# light_key_control.net
KiCad netlist of a schematic drawn in Altium Designer
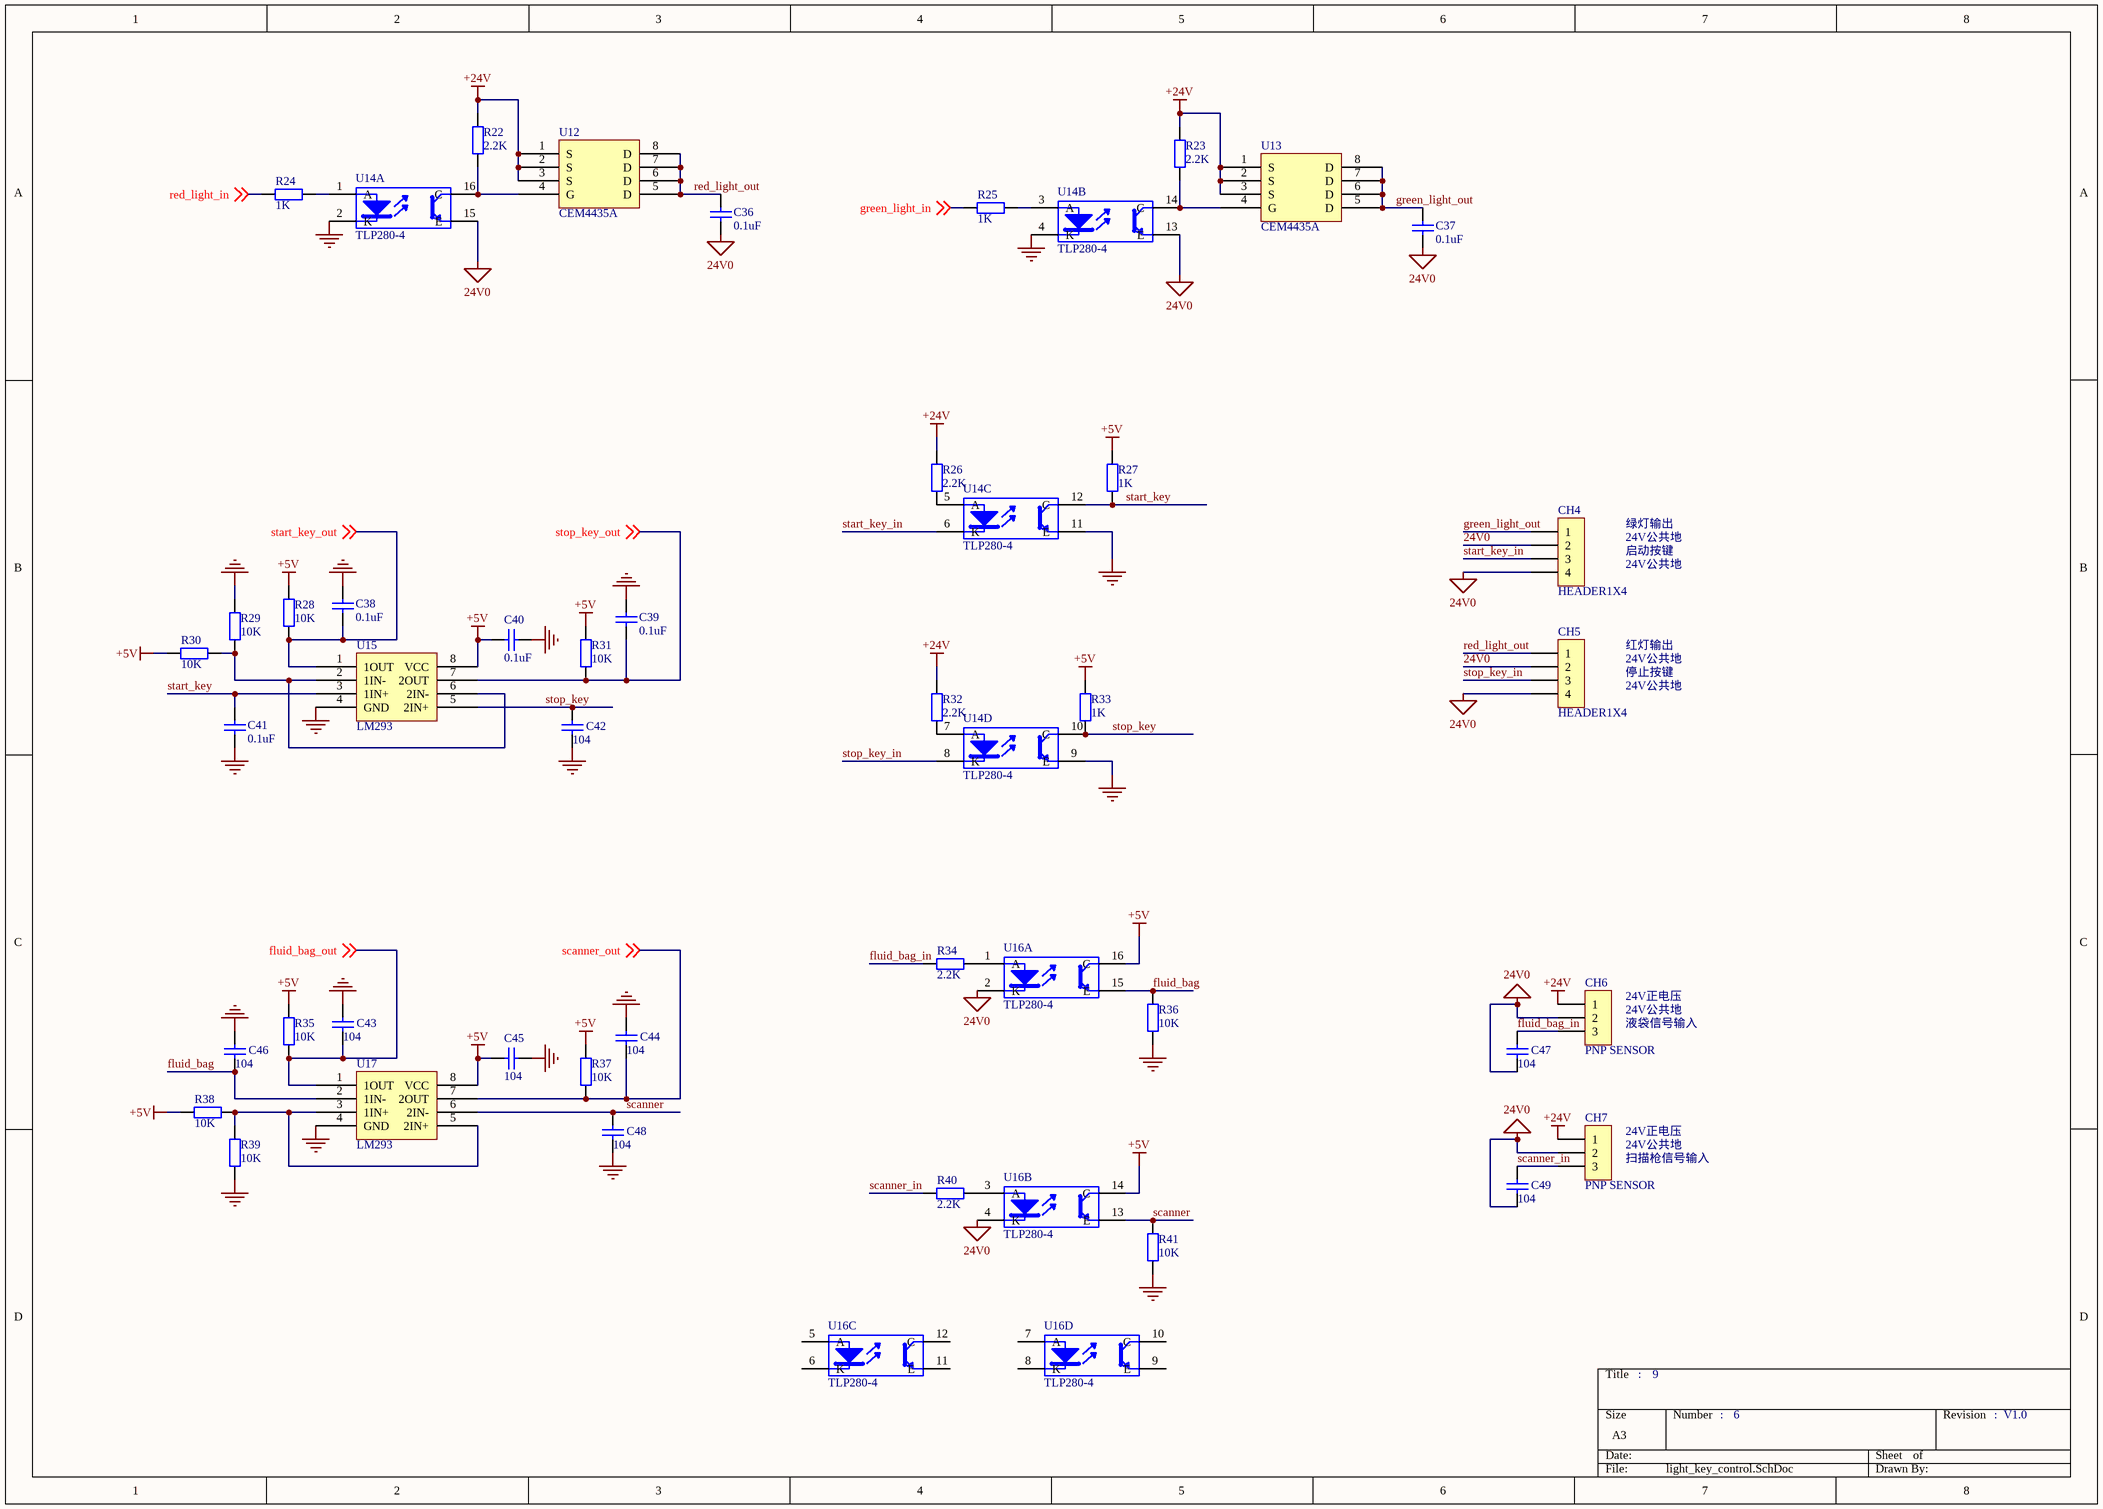
[diagram p0: light_key_control.SchDoc]

(export (version "E")
  (design (tool "Eeschema 10.0.6"))
  (components
    (comp (ref "C36")
      (value "0.1uF")
      (footprint "0805")
      (description "Capacitor")
      (fields (field (name "Comment") "Cap") (field (name "PUBLISHER") "Altium Limited"))
      (libsource (lib "Miscellaneous Devices") (part "Cap"))
    )
    (comp (ref "C37")
      (value "0.1uF")
      (footprint "0805")
      (description "Capacitor")
      (fields (field (name "Comment") "Cap") (field (name "PUBLISHER") "Altium Limited"))
      (libsource (lib "Miscellaneous Devices") (part "Cap"))
    )
    (comp (ref "C38")
      (value "0.1uF")
      (footprint "0805")
      (description "Capacitor")
      (fields (field (name "Comment") "Cap") (field (name "PUBLISHER") "Altium Limited"))
      (libsource (lib "Miscellaneous Devices") (part "Cap"))
    )
    (comp (ref "C39")
      (value "0.1uF")
      (footprint "0805")
      (description "Capacitor")
      (fields (field (name "Comment") "Cap") (field (name "PUBLISHER") "Altium Limited"))
      (libsource (lib "Miscellaneous Devices") (part "Cap"))
    )
    (comp (ref "C40")
      (value "0.1uF")
      (footprint "0805")
      (description "Capacitor")
      (fields (field (name "Comment") "Cap") (field (name "PUBLISHER") "Altium Limited"))
      (libsource (lib "Miscellaneous Devices") (part "Cap"))
    )
    (comp (ref "C41")
      (value "0.1uF")
      (footprint "0805")
      (description "Capacitor")
      (fields (field (name "Comment") "Cap") (field (name "PUBLISHER") "Altium Limited"))
      (libsource (lib "Miscellaneous Devices") (part "Cap"))
    )
    (comp (ref "C42")
      (value "104")
      (footprint "0805")
      (description "Capacitor")
      (fields (field (name "Comment") "Cap") (field (name "PUBLISHER") "Altium Limited"))
      (libsource (lib "Miscellaneous Devices") (part "Cap"))
    )
    (comp (ref "C43")
      (value "104")
      (footprint "0805")
      (description "Capacitor")
      (fields (field (name "Comment") "Cap") (field (name "PUBLISHER") "Altium Limited"))
      (libsource (lib "Miscellaneous Devices") (part "Cap"))
    )
    (comp (ref "C44")
      (value "104")
      (footprint "0805")
      (description "Capacitor")
      (fields (field (name "Comment") "Cap") (field (name "PUBLISHER") "Altium Limited"))
      (libsource (lib "Miscellaneous Devices") (part "Cap"))
    )
    (comp (ref "C45")
      (value "104")
      (footprint "0805")
      (description "Capacitor")
      (fields (field (name "Comment") "Cap") (field (name "PUBLISHER") "Altium Limited"))
      (libsource (lib "Miscellaneous Devices") (part "Cap"))
    )
    (comp (ref "C46")
      (value "104")
      (footprint "0805")
      (description "Capacitor")
      (fields (field (name "Comment") "Cap") (field (name "PUBLISHER") "Altium Limited"))
      (libsource (lib "Miscellaneous Devices") (part "Cap"))
    )
    (comp (ref "C47")
      (value "104")
      (footprint "0805")
      (description "Capacitor")
      (fields (field (name "Comment") "Cap") (field (name "PUBLISHER") "Altium Limited"))
      (libsource (lib "Miscellaneous Devices") (part "Cap"))
    )
    (comp (ref "C48")
      (value "104")
      (footprint "0805")
      (description "Capacitor")
      (fields (field (name "Comment") "Cap") (field (name "PUBLISHER") "Altium Limited"))
      (libsource (lib "Miscellaneous Devices") (part "Cap"))
    )
    (comp (ref "C49")
      (value "104")
      (footprint "0805")
      (description "Capacitor")
      (fields (field (name "Comment") "Cap") (field (name "PUBLISHER") "Altium Limited"))
      (libsource (lib "Miscellaneous Devices") (part "Cap"))
    )
    (comp (ref "CH4")
      (value "HEADER1X4")
      (footprint "CH3.96-4PIN")
      (libsource (lib "myIntegrated_Library1") (part "HEADER1X4"))
    )
    (comp (ref "CH5")
      (value "HEADER1X4")
      (footprint "CH3.96-4PIN")
      (libsource (lib "myIntegrated_Library1") (part "HEADER1X4"))
    )
    (comp (ref "CH6")
      (value "HEADER1X3")
      (footprint "CH3.96-3PIN")
      (fields (field (name "ALTIUM_UNNAMED_1") "PNP SENSOR"))
      (libsource (lib "myIntegrated_Library1") (part "HEADER1X3"))
    )
    (comp (ref "CH7")
      (value "HEADER1X3")
      (footprint "CH3.96-3PIN")
      (fields (field (name "ALTIUM_UNNAMED_1") "PNP SENSOR"))
      (libsource (lib "myIntegrated_Library1") (part "HEADER1X3"))
    )
    (comp (ref "R22")
      (value "2.2K")
      (footprint "0805")
      (description "Resistor")
      (fields (field (name "Comment") "Res2") (field (name "PUBLISHER") "Altium Limited"))
      (libsource (lib "") (part "Res2_1"))
    )
    (comp (ref "R23")
      (value "2.2K")
      (footprint "0805")
      (description "Resistor")
      (fields (field (name "Comment") "Res2") (field (name "PUBLISHER") "Altium Limited"))
      (libsource (lib "") (part "Res2_1"))
    )
    (comp (ref "R24")
      (value "1K")
      (footprint "0805")
      (description "Resistor")
      (fields (field (name "Comment") "Res2") (field (name "PUBLISHER") "Altium Limited"))
      (libsource (lib "") (part "Res2_3"))
    )
    (comp (ref "R25")
      (value "1K")
      (footprint "0805")
      (description "Resistor")
      (fields (field (name "Comment") "Res2") (field (name "PUBLISHER") "Altium Limited"))
      (libsource (lib "") (part "Res2_3"))
    )
    (comp (ref "R26")
      (value "2.2K")
      (footprint "0805")
      (description "Resistor")
      (fields (field (name "Comment") "Res2") (field (name "PUBLISHER") "Altium Limited"))
      (libsource (lib "Miscellaneous Devices") (part "Res2"))
    )
    (comp (ref "R27")
      (value "1K")
      (footprint "0805")
      (description "Resistor")
      (fields (field (name "Comment") "Res2") (field (name "PUBLISHER") "Altium Limited"))
      (libsource (lib "Miscellaneous Devices") (part "Res2"))
    )
    (comp (ref "R28")
      (value "10K")
      (footprint "0805")
      (description "Resistor")
      (fields (field (name "Comment") "Res2") (field (name "PUBLISHER") "Altium Limited"))
      (libsource (lib "Miscellaneous Devices") (part "Res2"))
    )
    (comp (ref "R29")
      (value "10K")
      (footprint "0805")
      (description "Resistor")
      (fields (field (name "Comment") "Res2") (field (name "PUBLISHER") "Altium Limited"))
      (libsource (lib "Miscellaneous Devices") (part "Res2"))
    )
    (comp (ref "R30")
      (value "10K")
      (footprint "0805")
      (description "Resistor")
      (fields (field (name "Comment") "Res2") (field (name "PUBLISHER") "Altium Limited"))
      (libsource (lib "") (part "Res2_2"))
    )
    (comp (ref "R31")
      (value "10K")
      (footprint "0805")
      (description "Resistor")
      (fields (field (name "Comment") "Res2") (field (name "PUBLISHER") "Altium Limited"))
      (libsource (lib "Miscellaneous Devices") (part "Res2"))
    )
    (comp (ref "R32")
      (value "2.2K")
      (footprint "0805")
      (description "Resistor")
      (fields (field (name "Comment") "Res2") (field (name "PUBLISHER") "Altium Limited"))
      (libsource (lib "Miscellaneous Devices") (part "Res2"))
    )
    (comp (ref "R33")
      (value "1K")
      (footprint "0805")
      (description "Resistor")
      (fields (field (name "Comment") "Res2") (field (name "PUBLISHER") "Altium Limited"))
      (libsource (lib "Miscellaneous Devices") (part "Res2"))
    )
    (comp (ref "R34")
      (value "2.2K")
      (footprint "0805")
      (description "Resistor")
      (fields (field (name "Comment") "Res2") (field (name "PUBLISHER") "Altium Limited"))
      (libsource (lib "") (part "Res2_2"))
    )
    (comp (ref "R35")
      (value "10K")
      (footprint "0805")
      (description "Resistor")
      (fields (field (name "Comment") "Res2") (field (name "PUBLISHER") "Altium Limited"))
      (libsource (lib "Miscellaneous Devices") (part "Res2"))
    )
    (comp (ref "R36")
      (value "10K")
      (footprint "0805")
      (description "Resistor")
      (fields (field (name "Comment") "Res2") (field (name "PUBLISHER") "Altium Limited"))
      (libsource (lib "Miscellaneous Devices") (part "Res2"))
    )
    (comp (ref "R37")
      (value "10K")
      (footprint "0805")
      (description "Resistor")
      (fields (field (name "Comment") "Res2") (field (name "PUBLISHER") "Altium Limited"))
      (libsource (lib "Miscellaneous Devices") (part "Res2"))
    )
    (comp (ref "R38")
      (value "10K")
      (footprint "0805")
      (description "Resistor")
      (fields (field (name "Comment") "Res2") (field (name "PUBLISHER") "Altium Limited"))
      (libsource (lib "") (part "Res2_2"))
    )
    (comp (ref "R39")
      (value "10K")
      (footprint "0805")
      (description "Resistor")
      (fields (field (name "Comment") "Res2") (field (name "PUBLISHER") "Altium Limited"))
      (libsource (lib "Miscellaneous Devices") (part "Res2"))
    )
    (comp (ref "R40")
      (value "2.2K")
      (footprint "0805")
      (description "Resistor")
      (fields (field (name "Comment") "Res2") (field (name "PUBLISHER") "Altium Limited"))
      (libsource (lib "") (part "Res2_2"))
    )
    (comp (ref "R41")
      (value "10K")
      (footprint "0805")
      (description "Resistor")
      (fields (field (name "Comment") "Res2") (field (name "PUBLISHER") "Altium Limited"))
      (libsource (lib "Miscellaneous Devices") (part "Res2"))
    )
    (comp (ref "U12")
      (value "CEM4435A")
      (footprint "SOP8-OP27")
      (libsource (lib "myIntegrated_Library1") (part "CEM4435A"))
    )
    (comp (ref "U13")
      (value "CEM4435A")
      (footprint "SOP8-OP27")
      (libsource (lib "myIntegrated_Library1") (part "CEM4435A"))
    )
    (comp (ref "U14") (value "TLP280-4") (footprint "SO16") (libsource (lib "WH V20") (part "TLP521-4")))
    (comp (ref "U15")
      (value "LM293")
      (footprint "SOP8-OP27")
      (libsource (lib "myIntegrated_Library1") (part "LM293"))
    )
    (comp (ref "U16") (value "TLP280-4") (footprint "SO16") (libsource (lib "WH V20") (part "TLP521-4")))
    (comp (ref "U17")
      (value "LM293")
      (footprint "SOP8-OP27")
      (libsource (lib "myIntegrated_Library1") (part "LM293"))
    )
  )
  (nets
    (net (code "1") (name "+5V") (class "Default")
      (node (ref "C40") (pin "2") (pinfunction "2_2") (pintype "passive"))
      (node (ref "C45") (pin "2") (pinfunction "2_2") (pintype "passive"))
      (node (ref "R27") (pin "1") (pinfunction "1_1") (pintype "passive"))
      (node (ref "R28") (pin "1") (pinfunction "1_1") (pintype "passive"))
      (node (ref "R30") (pin "1") (pinfunction "1_1") (pintype "passive"))
      (node (ref "R31") (pin "1") (pinfunction "1_1") (pintype "passive"))
      (node (ref "R33") (pin "1") (pinfunction "1_1") (pintype "passive"))
      (node (ref "R35") (pin "1") (pinfunction "1_1") (pintype "passive"))
      (node (ref "R37") (pin "1") (pinfunction "1_1") (pintype "passive"))
      (node (ref "R38") (pin "1") (pinfunction "1_1") (pintype "passive"))
      (node (ref "U15") (pin "8") (pinfunction "VCC_8") (pintype "passive"))
      (node (ref "U16") (pin "14") (pinfunction "C_14") (pintype "passive"))
      (node (ref "U16") (pin "16") (pinfunction "C_16") (pintype "passive"))
      (node (ref "U17") (pin "8") (pinfunction "VCC_8") (pintype "passive"))
    )
    (net (code "2") (name "+24V") (class "Default")
      (node (ref "CH6") (pin "1") (pinfunction "1_1") (pintype "passive"))
      (node (ref "CH7") (pin "1") (pinfunction "1_1") (pintype "passive"))
      (node (ref "R22") (pin "2") (pinfunction "2_2") (pintype "passive"))
      (node (ref "R23") (pin "2") (pinfunction "2_2") (pintype "passive"))
      (node (ref "R26") (pin "1") (pinfunction "1_1") (pintype "passive"))
      (node (ref "R32") (pin "1") (pinfunction "1_1") (pintype "passive"))
      (node (ref "U12") (pin "1") (pinfunction "S_1") (pintype "passive"))
      (node (ref "U12") (pin "2") (pinfunction "S_2") (pintype "passive"))
      (node (ref "U12") (pin "3") (pinfunction "S_3") (pintype "passive"))
      (node (ref "U13") (pin "1") (pinfunction "S_1") (pintype "passive"))
      (node (ref "U13") (pin "2") (pinfunction "S_2") (pintype "passive"))
      (node (ref "U13") (pin "3") (pinfunction "S_3") (pintype "passive"))
    )
    (net (code "3") (name "/fluid_bag") (class "Default")
      (node (ref "C46") (pin "1") (pinfunction "1_1") (pintype "passive"))
      (node (ref "R36") (pin "1") (pinfunction "1_1") (pintype "passive"))
      (node (ref "U16") (pin "15") (pinfunction "E_15") (pintype "passive"))
      (node (ref "U17") (pin "2") (pinfunction "1IN-_2") (pintype "passive"))
    )
    (net (code "4") (name "/fluid_bag_in") (class "Default")
      (node (ref "C47") (pin "2") (pinfunction "2_2") (pintype "passive"))
      (node (ref "CH6") (pin "3") (pinfunction "3_3") (pintype "passive"))
      (node (ref "R34") (pin "1") (pinfunction "1_1") (pintype "passive"))
    )
    (net (code "5") (name "/green_light_out") (class "Default")
      (node (ref "C37") (pin "1") (pinfunction "1_1") (pintype "passive"))
      (node (ref "CH4") (pin "1") (pinfunction "1_1") (pintype "passive"))
      (node (ref "U13") (pin "5") (pinfunction "D_5") (pintype "passive"))
      (node (ref "U13") (pin "6") (pinfunction "D_6") (pintype "passive"))
      (node (ref "U13") (pin "7") (pinfunction "D_7") (pintype "passive"))
      (node (ref "U13") (pin "8") (pinfunction "D_8") (pintype "passive"))
    )
    (net (code "6") (name "/red_light_out") (class "Default")
      (node (ref "C36") (pin "1") (pinfunction "1_1") (pintype "passive"))
      (node (ref "CH5") (pin "1") (pinfunction "1_1") (pintype "passive"))
      (node (ref "U12") (pin "5") (pinfunction "D_5") (pintype "passive"))
      (node (ref "U12") (pin "6") (pinfunction "D_6") (pintype "passive"))
      (node (ref "U12") (pin "7") (pinfunction "D_7") (pintype "passive"))
      (node (ref "U12") (pin "8") (pinfunction "D_8") (pintype "passive"))
    )
    (net (code "7") (name "/scanner") (class "Default")
      (node (ref "C48") (pin "2") (pinfunction "2_2") (pintype "passive"))
      (node (ref "R41") (pin "1") (pinfunction "1_1") (pintype "passive"))
      (node (ref "U16") (pin "13") (pinfunction "E_13") (pintype "passive"))
      (node (ref "U17") (pin "6") (pinfunction "2IN-_6") (pintype "passive"))
    )
    (net (code "8") (name "/scanner_in") (class "Default")
      (node (ref "C49") (pin "2") (pinfunction "2_2") (pintype "passive"))
      (node (ref "CH7") (pin "3") (pinfunction "3_3") (pintype "passive"))
      (node (ref "R40") (pin "1") (pinfunction "1_1") (pintype "passive"))
    )
    (net (code "9") (name "/start_key") (class "Default")
      (node (ref "C41") (pin "2") (pinfunction "2_2") (pintype "passive"))
      (node (ref "R27") (pin "2") (pinfunction "2_2") (pintype "passive"))
      (node (ref "U14") (pin "12") (pinfunction "C_12") (pintype "passive"))
      (node (ref "U15") (pin "3") (pinfunction "1IN+_3") (pintype "passive"))
    )
    (net (code "10") (name "/start_key_in") (class "Default")
      (node (ref "CH4") (pin "3") (pinfunction "3_3") (pintype "passive"))
      (node (ref "U14") (pin "6") (pinfunction "K_6") (pintype "passive"))
    )
    (net (code "11") (name "/stop_key") (class "Default")
      (node (ref "C42") (pin "2") (pinfunction "2_2") (pintype "passive"))
      (node (ref "R33") (pin "2") (pinfunction "2_2") (pintype "passive"))
      (node (ref "U14") (pin "10") (pinfunction "C_10") (pintype "passive"))
      (node (ref "U15") (pin "5") (pinfunction "2IN+_5") (pintype "passive"))
    )
    (net (code "12") (name "/stop_key_in") (class "Default")
      (node (ref "CH5") (pin "3") (pinfunction "3_3") (pintype "passive"))
      (node (ref "U14") (pin "8") (pinfunction "K_8") (pintype "passive"))
    )
    (net (code "13") (name "24V0") (class "Default")
      (node (ref "C36") (pin "2") (pinfunction "2_2") (pintype "passive"))
      (node (ref "C37") (pin "2") (pinfunction "2_2") (pintype "passive"))
      (node (ref "C47") (pin "1") (pinfunction "1_1") (pintype "passive"))
      (node (ref "C49") (pin "1") (pinfunction "1_1") (pintype "passive"))
      (node (ref "CH4") (pin "2") (pinfunction "2_2") (pintype "passive"))
      (node (ref "CH4") (pin "4") (pinfunction "4_4") (pintype "passive"))
      (node (ref "CH5") (pin "2") (pinfunction "2_2") (pintype "passive"))
      (node (ref "CH5") (pin "4") (pinfunction "4_4") (pintype "passive"))
      (node (ref "CH6") (pin "2") (pinfunction "2_2") (pintype "passive"))
      (node (ref "CH7") (pin "2") (pinfunction "2_2") (pintype "passive"))
      (node (ref "U14") (pin "13") (pinfunction "E_13") (pintype "passive"))
      (node (ref "U14") (pin "15") (pinfunction "E_15") (pintype "passive"))
      (node (ref "U16") (pin "2") (pinfunction "K_2") (pintype "passive"))
      (node (ref "U16") (pin "4") (pinfunction "K_4") (pintype "passive"))
    )
    (net (code "14") (name "GND") (class "Default")
      (node (ref "C38") (pin "1") (pinfunction "1_1") (pintype "passive"))
      (node (ref "C39") (pin "1") (pinfunction "1_1") (pintype "passive"))
      (node (ref "C40") (pin "1") (pinfunction "1_1") (pintype "passive"))
      (node (ref "C41") (pin "1") (pinfunction "1_1") (pintype "passive"))
      (node (ref "C42") (pin "1") (pinfunction "1_1") (pintype "passive"))
      (node (ref "C43") (pin "2") (pinfunction "2_2") (pintype "passive"))
      (node (ref "C44") (pin "2") (pinfunction "2_2") (pintype "passive"))
      (node (ref "C45") (pin "1") (pinfunction "1_1") (pintype "passive"))
      (node (ref "C46") (pin "2") (pinfunction "2_2") (pintype "passive"))
      (node (ref "C48") (pin "1") (pinfunction "1_1") (pintype "passive"))
      (node (ref "R29") (pin "1") (pinfunction "1_1") (pintype "passive"))
      (node (ref "R36") (pin "2") (pinfunction "2_2") (pintype "passive"))
      (node (ref "R39") (pin "2") (pinfunction "2_2") (pintype "passive"))
      (node (ref "R41") (pin "2") (pinfunction "2_2") (pintype "passive"))
      (node (ref "U14") (pin "11") (pinfunction "E_11") (pintype "passive"))
      (node (ref "U14") (pin "2") (pinfunction "K_2") (pintype "passive"))
      (node (ref "U14") (pin "4") (pinfunction "K_4") (pintype "passive"))
      (node (ref "U14") (pin "9") (pinfunction "E_9") (pintype "passive"))
      (node (ref "U15") (pin "4") (pinfunction "GND_4") (pintype "passive"))
      (node (ref "U17") (pin "4") (pinfunction "GND_4") (pintype "passive"))
    )
    (net (code "15") (name "Net-(U12-G)") (class "Default")
      (node (ref "R22") (pin "1") (pinfunction "1_1") (pintype "passive"))
      (node (ref "U12") (pin "4") (pinfunction "G_4") (pintype "passive"))
      (node (ref "U14") (pin "16") (pinfunction "C_16") (pintype "passive"))
    )
    (net (code "16") (name "Net-(U13-G)") (class "Default")
      (node (ref "R23") (pin "1") (pinfunction "1_1") (pintype "passive"))
      (node (ref "U13") (pin "4") (pinfunction "G_4") (pintype "passive"))
      (node (ref "U14") (pin "14") (pinfunction "C_14") (pintype "passive"))
    )
    (net (code "17") (name "Net-(U14A-A)") (class "Default")
      (node (ref "R24") (pin "1") (pinfunction "1_1") (pintype "passive"))
      (node (ref "U14") (pin "1") (pinfunction "A_1") (pintype "passive"))
    )
    (net (code "18") (name "Net-(U14B-A)") (class "Default")
      (node (ref "R25") (pin "1") (pinfunction "1_1") (pintype "passive"))
      (node (ref "U14") (pin "3") (pinfunction "A_3") (pintype "passive"))
    )
    (net (code "19") (name "Net-(U14C-A)") (class "Default")
      (node (ref "R26") (pin "2") (pinfunction "2_2") (pintype "passive"))
      (node (ref "U14") (pin "5") (pinfunction "A_5") (pintype "passive"))
    )
    (net (code "20") (name "Net-(U14D-A)") (class "Default")
      (node (ref "R32") (pin "2") (pinfunction "2_2") (pintype "passive"))
      (node (ref "U14") (pin "7") (pinfunction "A_7") (pintype "passive"))
    )
    (net (code "21") (name "Net-(U15-1IN-)") (class "Default")
      (node (ref "R29") (pin "2") (pinfunction "2_2") (pintype "passive"))
      (node (ref "R30") (pin "2") (pinfunction "2_2") (pintype "passive"))
      (node (ref "U15") (pin "2") (pinfunction "1IN-_2") (pintype "passive"))
      (node (ref "U15") (pin "6") (pinfunction "2IN-_6") (pintype "passive"))
    )
    (net (code "22") (name "Net-(U16A-A)") (class "Default")
      (node (ref "R34") (pin "2") (pinfunction "2_2") (pintype "passive"))
      (node (ref "U16") (pin "1") (pinfunction "A_1") (pintype "passive"))
    )
    (net (code "23") (name "Net-(U16B-A)") (class "Default")
      (node (ref "R40") (pin "2") (pinfunction "2_2") (pintype "passive"))
      (node (ref "U16") (pin "3") (pinfunction "A_3") (pintype "passive"))
    )
    (net (code "24") (name "Net-(U17-1IN+)") (class "Default")
      (node (ref "R38") (pin "2") (pinfunction "2_2") (pintype "passive"))
      (node (ref "R39") (pin "1") (pinfunction "1_1") (pintype "passive"))
      (node (ref "U17") (pin "3") (pinfunction "1IN+_3") (pintype "passive"))
      (node (ref "U17") (pin "5") (pinfunction "2IN+_5") (pintype "passive"))
    )
    (net (code "25") (name "fluid_bag_out") (class "Default")
      (node (ref "C43") (pin "1") (pinfunction "1_1") (pintype "passive"))
      (node (ref "R35") (pin "2") (pinfunction "2_2") (pintype "passive"))
      (node (ref "U17") (pin "1") (pinfunction "1OUT_1") (pintype "passive"))
    )
    (net (code "26") (name "green_light_in") (class "Default")
      (node (ref "R25") (pin "2") (pinfunction "2_2") (pintype "passive"))
    )
    (net (code "27") (name "red_light_in") (class "Default")
      (node (ref "R24") (pin "2") (pinfunction "2_2") (pintype "passive"))
    )
    (net (code "28") (name "scanner_out") (class "Default")
      (node (ref "C44") (pin "1") (pinfunction "1_1") (pintype "passive"))
      (node (ref "R37") (pin "2") (pinfunction "2_2") (pintype "passive"))
      (node (ref "U17") (pin "7") (pinfunction "2OUT_7") (pintype "passive"))
    )
    (net (code "29") (name "start_key_out") (class "Default")
      (node (ref "C38") (pin "2") (pinfunction "2_2") (pintype "passive"))
      (node (ref "R28") (pin "2") (pinfunction "2_2") (pintype "passive"))
      (node (ref "U15") (pin "1") (pinfunction "1OUT_1") (pintype "passive"))
    )
    (net (code "30") (name "stop_key_out") (class "Default")
      (node (ref "C39") (pin "2") (pinfunction "2_2") (pintype "passive"))
      (node (ref "R31") (pin "2") (pinfunction "2_2") (pintype "passive"))
      (node (ref "U15") (pin "7") (pinfunction "2OUT_7") (pintype "passive"))
    )
    (net (code "31") (name "unconnected-(U16C-A-Pad5)") (class "Default")
      (node (ref "U16") (pin "5") (pinfunction "A_5") (pintype "passive"))
    )
    (net (code "32") (name "unconnected-(U16C-C-Pad12)") (class "Default")
      (node (ref "U16") (pin "12") (pinfunction "C_12") (pintype "passive"))
    )
    (net (code "33") (name "unconnected-(U16C-E-Pad11)") (class "Default")
      (node (ref "U16") (pin "11") (pinfunction "E_11") (pintype "passive"))
    )
    (net (code "34") (name "unconnected-(U16C-K-Pad6)") (class "Default")
      (node (ref "U16") (pin "6") (pinfunction "K_6") (pintype "passive"))
    )
    (net (code "35") (name "unconnected-(U16D-A-Pad7)") (class "Default")
      (node (ref "U16") (pin "7") (pinfunction "A_7") (pintype "passive"))
    )
    (net (code "36") (name "unconnected-(U16D-C-Pad10)") (class "Default")
      (node (ref "U16") (pin "10") (pinfunction "C_10") (pintype "passive"))
    )
    (net (code "37") (name "unconnected-(U16D-E-Pad9)") (class "Default")
      (node (ref "U16") (pin "9") (pinfunction "E_9") (pintype "passive"))
    )
    (net (code "38") (name "unconnected-(U16D-K-Pad8)") (class "Default")
      (node (ref "U16") (pin "8") (pinfunction "K_8") (pintype "passive"))
    )
  )
)
